# High_Side_FETs_Parallel.net
KiCad netlist of a schematic drawn in Altium Designer
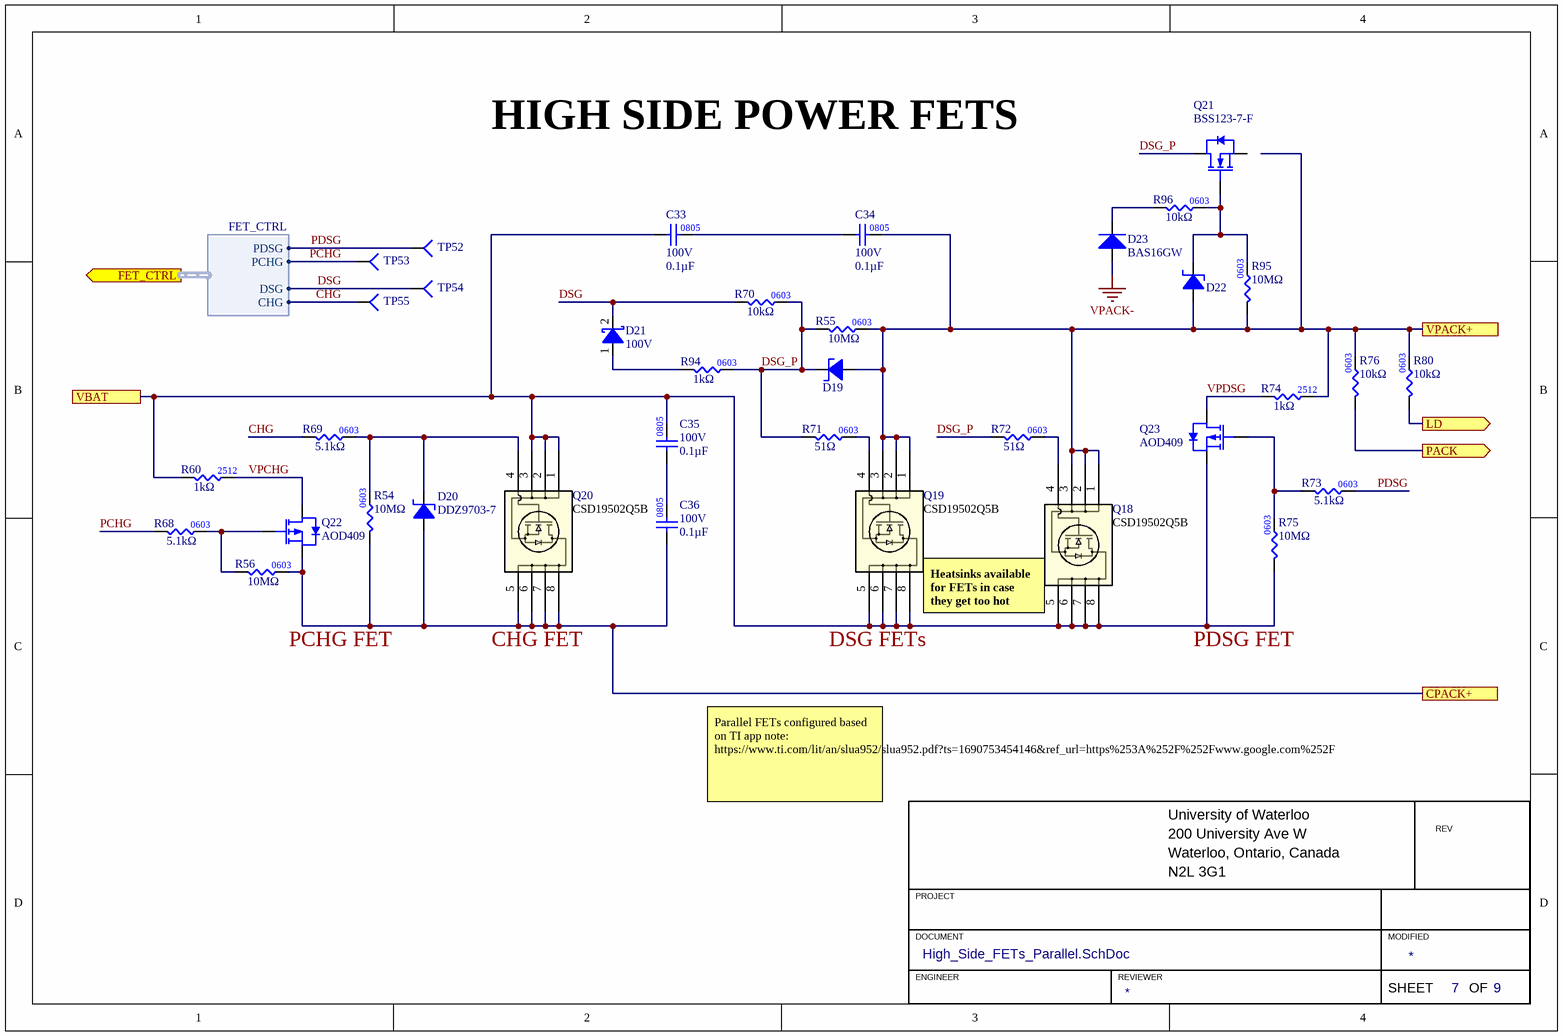
[diagram p0: High_Side_FETs_Parallel.SchDoc]

(export (version "E")
  (design (tool "Eeschema 10.0.6"))
  (components
    (comp (ref "C33")
      (value "0.1µF")
      (footprint "CAP0805")
      (description "CAP CER 0.1UF 100V X7R 0805")
      (fields (field (name "VOLTAGE RATING") "100V") (field (name "Comment") "CAP_0.1uF_100V_0805"))
      (libsource (lib "Personal_Schematic_Library_2022") (part "CAP_0.1uF_100V_0805"))
    )
    (comp (ref "C34")
      (value "0.1µF")
      (footprint "CAP0805")
      (description "CAP CER 0.1UF 100V X7R 0805")
      (fields (field (name "VOLTAGE RATING") "100V") (field (name "Comment") "CAP_0.1uF_100V_0805"))
      (libsource (lib "Personal_Schematic_Library_2022") (part "CAP_0.1uF_100V_0805"))
    )
    (comp (ref "C35")
      (value "0.1µF")
      (footprint "CAP0805")
      (description "CAP CER 0.1UF 100V X7R 0805")
      (fields (field (name "VOLTAGE RATING") "100V") (field (name "Comment") "CAP_0.1uF_100V_0805"))
      (libsource (lib "Personal_Schematic_Library_2022") (part "CAP_0.1uF_100V_0805"))
    )
    (comp (ref "C36")
      (value "0.1µF")
      (footprint "CAP0805")
      (description "CAP CER 0.1UF 100V X7R 0805")
      (fields (field (name "VOLTAGE RATING") "100V") (field (name "Comment") "CAP_0.1uF_100V_0805"))
      (libsource (lib "Personal_Schematic_Library_2022") (part "CAP_0.1uF_100V_0805"))
    )
    (comp (ref "D19")
      (value "DIO_ZENER_16V")
      (footprint "SOD-123_FLAT")
      (description "DIODE ZENER 16V 500MW SOD123")
      (libsource (lib "Personal_Schematic_Library_2022") (part "DIO_ZENER_16V"))
    )
    (comp (ref "D20")
      (value "DIO_ZENER_16V")
      (footprint "SOD-123_FLAT")
      (description "DIODE ZENER 16V 500MW SOD123")
      (fields (field (name "MANUFACTURER PART NUMBER 1") "DDZ9703-7"))
      (libsource (lib "Personal_Schematic_Library_2022") (part "DIO_ZENER_16V"))
    )
    (comp (ref "D21")
      (value "DIO_SCHOTTKY_100V_1A")
      (footprint "SOD-123_FLAT")
      (description "DIODE SCHOTTKY 100V 1A SOD-123F")
      (fields (field (name "VR (MAX)") "100V"))
      (libsource (lib "Personal_Schematic_Library_2022") (part "DIO_SCHOTTKY_100V_1A"))
    )
    (comp (ref "D22")
      (value "DIO_ZENER_16V")
      (footprint "SOD-123_FLAT")
      (description "DIODE ZENER 16V 500MW SOD123")
      (libsource (lib "Personal_Schematic_Library_2022") (part "DIO_ZENER_16V"))
    )
    (comp (ref "D23")
      (value "DIO_100V_215mA")
      (footprint "DIODSOD-123")
      (description "DIODE GEN PURP 100V 215MA SOD123")
      (fields (field (name "MANUFACTURER PART NUMBER 1") "BAS16GW"))
      (libsource (lib "Personal_Schematic_Library_2022") (part "DIO_100V_215mA"))
    )
    (comp (ref "Q18")
      (value "CSD19502Q5B")
      (footprint "DFN5060")
      (description "MOSFET N-CH 80V 100A 8VSON")
      (fields (field (name "MANUFACTURER PART NUMBER 1") "CSD19502Q5B"))
      (libsource (lib "Personal_Schematic_Library_2022") (part "NMOS_CSD19502Q5B_80V_100A"))
    )
    (comp (ref "Q19")
      (value "CSD19502Q5B")
      (footprint "DFN5060")
      (description "MOSFET N-CH 80V 100A 8VSON")
      (fields (field (name "MANUFACTURER PART NUMBER 1") "CSD19502Q5B"))
      (libsource (lib "Personal_Schematic_Library_2022") (part "NMOS_CSD19502Q5B_80V_100A"))
    )
    (comp (ref "Q20")
      (value "CSD19502Q5B")
      (footprint "DFN5060")
      (description "MOSFET N-CH 80V 100A 8VSON")
      (fields (field (name "MANUFACTURER PART NUMBER 1") "CSD19502Q5B"))
      (libsource (lib "Personal_Schematic_Library_2022") (part "NMOS_CSD19502Q5B_80V_100A"))
    )
    (comp (ref "Q21")
      (value "NMOS_100V_170mA")
      (footprint "SOT23-3")
      (description "MOSFET N-CH 100V 170MA SOT23-3")
      (fields (field (name "MANUFACTURER PART NUMBER 1") "BSS123-7-F"))
      (libsource (lib "Personal_Schematic_Library_2022") (part "NMOS_100V_170mA"))
    )
    (comp (ref "Q22")
      (value "PMOS_60V_26A")
      (footprint "TO-252 AOSMD")
      (description "MOSFET P-CH 60V 26A TO252")
      (fields (field (name "MANUFACTURER PART NUMBER 1") "AOD409"))
      (libsource (lib "Personal_Schematic_Library_2022") (part "PMOS_60V_26A"))
    )
    (comp (ref "Q23")
      (value "PMOS_60V_26A")
      (footprint "TO-252 AOSMD")
      (description "MOSFET P-CH 60V 26A TO252")
      (fields (field (name "MANUFACTURER PART NUMBER 1") "AOD409"))
      (libsource (lib "Personal_Schematic_Library_2022") (part "PMOS_60V_26A"))
    )
    (comp (ref "R54")
      (value "10MΩ")
      (footprint "RES0603")
      (description "RES 10M OHM 1% 1/10W 0603")
      (fields (field (name "Comment") "RES_10MΩ_0603_1%"))
      (libsource (lib "Personal_Schematic_Library_2022") (part "RES_10MΩ_0603_1%"))
    )
    (comp (ref "R55")
      (value "10MΩ")
      (footprint "RES0603")
      (description "RES 10M OHM 1% 1/10W 0603")
      (fields (field (name "Comment") "RES_10MΩ_0603_1%"))
      (libsource (lib "Personal_Schematic_Library_2022") (part "RES_10MΩ_0603_1%"))
    )
    (comp (ref "R56")
      (value "10MΩ")
      (footprint "RES0603")
      (description "RES 10M OHM 1% 1/10W 0603")
      (fields (field (name "Comment") "RES_10MΩ_0603_1%"))
      (libsource (lib "Personal_Schematic_Library_2022") (part "RES_10MΩ_0603_1%"))
    )
    (comp (ref "R60")
      (value "1kΩ")
      (footprint "RES2512")
      (description "RES SMD 1K OHM 1% 3W 2512")
      (fields (field (name "Comment") "RES_1kΩ_2512_1%"))
      (libsource (lib "Personal_Schematic_Library_2022") (part "RES_1kΩ_2512_1%"))
    )
    (comp (ref "R68")
      (value "5.1kΩ")
      (footprint "RES0603")
      (description "RES 5.1K OHM 1% 1/10W 0603")
      (fields (field (name "Comment") "RES_5.1kΩ_0603_1%"))
      (libsource (lib "Personal_Schematic_Library_2022") (part "RES_5.1kΩ_0603_1%"))
    )
    (comp (ref "R69")
      (value "5.1kΩ")
      (footprint "RES0603")
      (description "RES 5.1K OHM 1% 1/10W 0603")
      (fields (field (name "Comment") "RES_5.1kΩ_0603_1%"))
      (libsource (lib "Personal_Schematic_Library_2022") (part "RES_5.1kΩ_0603_1%"))
    )
    (comp (ref "R70")
      (value "10kΩ")
      (footprint "RES0603")
      (description "RES 10K OHM 1% 1/8W 0603")
      (fields (field (name "Comment") "RES_10kΩ_0603_1%"))
      (libsource (lib "Personal_Schematic_Library_2022") (part "RES_10kΩ_0603_1%"))
    )
    (comp (ref "R71")
      (value "51Ω")
      (footprint "RES0603")
      (description "RES 51 OHM 1% 1/10W 0603")
      (fields (field (name "Comment") "RES_51Ω_0603_1%"))
      (libsource (lib "Personal_Schematic_Library_2022") (part "RES_51Ω_0603_1%"))
    )
    (comp (ref "R72")
      (value "51Ω")
      (footprint "RES0603")
      (description "RES 51 OHM 1% 1/10W 0603")
      (fields (field (name "Comment") "RES_51Ω_0603_1%"))
      (libsource (lib "Personal_Schematic_Library_2022") (part "RES_51Ω_0603_1%"))
    )
    (comp (ref "R73")
      (value "5.1kΩ")
      (footprint "RES0603")
      (description "RES 5.1K OHM 1% 1/10W 0603")
      (fields (field (name "Comment") "RES_5.1kΩ_0603_1%"))
      (libsource (lib "Personal_Schematic_Library_2022") (part "RES_5.1kΩ_0603_1%"))
    )
    (comp (ref "R74")
      (value "1kΩ")
      (footprint "RES2512")
      (description "RES SMD 1K OHM 1% 3W 2512")
      (fields (field (name "Comment") "RES_1kΩ_2512_1%"))
      (libsource (lib "Personal_Schematic_Library_2022") (part "RES_1kΩ_2512_1%"))
    )
    (comp (ref "R75")
      (value "10MΩ")
      (footprint "RES0603")
      (description "RES 10M OHM 1% 1/10W 0603")
      (fields (field (name "Comment") "RES_10MΩ_0603_1%"))
      (libsource (lib "Personal_Schematic_Library_2022") (part "RES_10MΩ_0603_1%"))
    )
    (comp (ref "R76")
      (value "10kΩ")
      (footprint "RES0603")
      (description "RES 10K OHM 1% 1/8W 0603")
      (fields (field (name "Comment") "RES_10kΩ_0603_1%"))
      (libsource (lib "Personal_Schematic_Library_2022") (part "RES_10kΩ_0603_1%"))
    )
    (comp (ref "R80")
      (value "10kΩ")
      (footprint "RES0603")
      (description "RES 10K OHM 1% 1/8W 0603")
      (fields (field (name "Comment") "RES_10kΩ_0603_1%"))
      (libsource (lib "Personal_Schematic_Library_2022") (part "RES_10kΩ_0603_1%"))
    )
    (comp (ref "R94")
      (value "1kΩ")
      (footprint "RES0603")
      (description "RES 1K OHM 1% 1/8W 0603")
      (fields (field (name "Comment") "RES_1kΩ_0603_1%"))
      (libsource (lib "Personal_Schematic_Library_2022") (part "RES_1kΩ_0603_1%"))
    )
    (comp (ref "R95")
      (value "10MΩ")
      (footprint "RES0603")
      (description "RES 10M OHM 1% 1/10W 0603")
      (fields (field (name "Comment") "RES_10MΩ_0603_1%"))
      (libsource (lib "Personal_Schematic_Library_2022") (part "RES_10MΩ_0603_1%"))
    )
    (comp (ref "R96")
      (value "10kΩ")
      (footprint "RES0603")
      (description "RES 10K OHM 1% 1/8W 0603")
      (fields (field (name "Comment") "RES_10kΩ_0603_1%"))
      (libsource (lib "Personal_Schematic_Library_2022") (part "RES_10kΩ_0603_1%"))
    )
    (comp (ref "TP52")
      (value "TESTPOINT_1MM_CIRCLE")
      (footprint "TESTPOINT_CIRCLE_1MM")
      (description "TESTPOINT 1MM CIRCLE")
      (libsource (lib "Personal_Schematic_Library_2022") (part "TESTPOINT_1MM_CIRCLE"))
    )
    (comp (ref "TP53")
      (value "TESTPOINT_1MM_CIRCLE")
      (footprint "TESTPOINT_CIRCLE_1MM")
      (description "TESTPOINT 1MM CIRCLE")
      (libsource (lib "Personal_Schematic_Library_2022") (part "TESTPOINT_1MM_CIRCLE"))
    )
    (comp (ref "TP54")
      (value "TESTPOINT_1MM_CIRCLE")
      (footprint "TESTPOINT_CIRCLE_1MM")
      (description "TESTPOINT 1MM CIRCLE")
      (libsource (lib "Personal_Schematic_Library_2022") (part "TESTPOINT_1MM_CIRCLE"))
    )
    (comp (ref "TP55")
      (value "TESTPOINT_1MM_CIRCLE")
      (footprint "TESTPOINT_CIRCLE_1MM")
      (description "TESTPOINT 1MM CIRCLE")
      (libsource (lib "Personal_Schematic_Library_2022") (part "TESTPOINT_1MM_CIRCLE"))
    )
  )
  (nets
    (net (code "2") (name "/CHG") (class "Default")
      (node (ref "R69") (pin "1") (pinfunction "1_1") (pintype "passive"))
      (node (ref "TP55") (pin "1") (pinfunction "=value_1") (pintype "passive"))
    )
    (net (code "3") (name "/CPACK+") (class "Default")
      (node (ref "C36") (pin "1") (pinfunction "1_1") (pintype "passive"))
      (node (ref "D20") (pin "1") (pinfunction "Anode_1") (pintype "passive"))
      (node (ref "Q20") (pin "5") (pinfunction "D_5") (pintype "passive"))
      (node (ref "Q20") (pin "6") (pinfunction "D_6") (pintype "passive"))
      (node (ref "Q20") (pin "7") (pinfunction "D_7") (pintype "passive"))
      (node (ref "Q20") (pin "8") (pinfunction "D_8") (pintype "passive"))
      (node (ref "Q22") (pin "3") (pinfunction "Source_3") (pintype "passive"))
      (node (ref "R54") (pin "1") (pinfunction "1_1") (pintype "passive"))
      (node (ref "R56") (pin "2") (pinfunction "2_2") (pintype "passive"))
    )
    (net (code "4") (name "/DSG") (class "Default")
      (node (ref "D21") (pin "2") (pinfunction "Cathode_2") (pintype "passive"))
      (node (ref "R70") (pin "1") (pinfunction "1_1") (pintype "passive"))
      (node (ref "TP54") (pin "1") (pinfunction "=value_1") (pintype "passive"))
    )
    (net (code "5") (name "/DSG_P") (class "Default")
      (node (ref "D19") (pin "2") (pinfunction "Cathode_2") (pintype "passive"))
      (node (ref "Q21") (pin "3") (pinfunction "DRAIN_3") (pintype "passive"))
      (node (ref "R55") (pin "1") (pinfunction "1_1") (pintype "passive"))
      (node (ref "R70") (pin "2") (pinfunction "2_2") (pintype "passive"))
      (node (ref "R71") (pin "1") (pinfunction "1_1") (pintype "passive"))
      (node (ref "R72") (pin "1") (pinfunction "1_1") (pintype "passive"))
      (node (ref "R94") (pin "2") (pinfunction "2_2") (pintype "passive"))
    )
    (net (code "6") (name "/LD") (class "Default")
      (node (ref "R80") (pin "1") (pinfunction "1_1") (pintype "passive"))
    )
    (net (code "7") (name "/PACK") (class "Default")
      (node (ref "R76") (pin "1") (pinfunction "1_1") (pintype "passive"))
    )
    (net (code "8") (name "/PCHG") (class "Default")
      (node (ref "R68") (pin "1") (pinfunction "1_1") (pintype "passive"))
      (node (ref "TP53") (pin "1") (pinfunction "=value_1") (pintype "passive"))
    )
    (net (code "9") (name "/PDSG") (class "Default")
      (node (ref "R73") (pin "2") (pinfunction "2_2") (pintype "passive"))
      (node (ref "TP52") (pin "1") (pinfunction "=value_1") (pintype "passive"))
    )
    (net (code "10") (name "/VBAT") (class "Default")
      (node (ref "C33") (pin "1") (pinfunction "1_1") (pintype "passive"))
      (node (ref "C35") (pin "2") (pinfunction "2_2") (pintype "passive"))
      (node (ref "Q18") (pin "5") (pinfunction "D_5") (pintype "passive"))
      (node (ref "Q18") (pin "6") (pinfunction "D_6") (pintype "passive"))
      (node (ref "Q18") (pin "7") (pinfunction "D_7") (pintype "passive"))
      (node (ref "Q18") (pin "8") (pinfunction "D_8") (pintype "passive"))
      (node (ref "Q19") (pin "5") (pinfunction "D_5") (pintype "passive"))
      (node (ref "Q19") (pin "6") (pinfunction "D_6") (pintype "passive"))
      (node (ref "Q19") (pin "7") (pinfunction "D_7") (pintype "passive"))
      (node (ref "Q19") (pin "8") (pinfunction "D_8") (pintype "passive"))
      (node (ref "Q20") (pin "1") (pinfunction "S_1") (pintype "passive"))
      (node (ref "Q20") (pin "2") (pinfunction "S_2") (pintype "passive"))
      (node (ref "Q20") (pin "3") (pinfunction "S_3") (pintype "passive"))
      (node (ref "Q23") (pin "3") (pinfunction "Source_3") (pintype "passive"))
      (node (ref "R60") (pin "1") (pinfunction "1_1") (pintype "passive"))
      (node (ref "R75") (pin "1") (pinfunction "1_1") (pintype "passive"))
    )
    (net (code "11") (name "/VPACK+") (class "Default")
      (node (ref "C34") (pin "2") (pinfunction "2_2") (pintype "passive"))
      (node (ref "D19") (pin "1") (pinfunction "Anode_1") (pintype "passive"))
      (node (ref "D22") (pin "1") (pinfunction "Anode_1") (pintype "passive"))
      (node (ref "Q18") (pin "1") (pinfunction "S_1") (pintype "passive"))
      (node (ref "Q18") (pin "2") (pinfunction "S_2") (pintype "passive"))
      (node (ref "Q18") (pin "3") (pinfunction "S_3") (pintype "passive"))
      (node (ref "Q19") (pin "1") (pinfunction "S_1") (pintype "passive"))
      (node (ref "Q19") (pin "2") (pinfunction "S_2") (pintype "passive"))
      (node (ref "Q19") (pin "3") (pinfunction "S_3") (pintype "passive"))
      (node (ref "R55") (pin "2") (pinfunction "2_2") (pintype "passive"))
      (node (ref "R74") (pin "2") (pinfunction "2_2") (pintype "passive"))
      (node (ref "R76") (pin "2") (pinfunction "2_2") (pintype "passive"))
      (node (ref "R80") (pin "2") (pinfunction "2_2") (pintype "passive"))
      (node (ref "R95") (pin "1") (pinfunction "1_1") (pintype "passive"))
    )
    (net (code "12") (name "/VPCHG") (class "Default")
      (node (ref "Q22") (pin "2") (pinfunction "Drain_2") (pintype "passive"))
      (node (ref "R60") (pin "2") (pinfunction "2_2") (pintype "passive"))
    )
    (net (code "13") (name "/VPDSG") (class "Default")
      (node (ref "Q23") (pin "2") (pinfunction "Drain_2") (pintype "passive"))
      (node (ref "R74") (pin "1") (pinfunction "1_1") (pintype "passive"))
    )
    (net (code "15") (name "Net-(C33-Pad2)") (class "Default")
      (node (ref "C33") (pin "2") (pinfunction "2_2") (pintype "passive"))
      (node (ref "C34") (pin "1") (pinfunction "1_1") (pintype "passive"))
    )
    (net (code "16") (name "Net-(C35-Pad1)") (class "Default")
      (node (ref "C35") (pin "1") (pinfunction "1_1") (pintype "passive"))
      (node (ref "C36") (pin "2") (pinfunction "2_2") (pintype "passive"))
    )
    (net (code "17") (name "Net-(D20-Cathode)") (class "Default")
      (node (ref "D20") (pin "2") (pinfunction "Cathode_2") (pintype "passive"))
      (node (ref "Q20") (pin "4") (pinfunction "G_4") (pintype "passive"))
      (node (ref "R54") (pin "2") (pinfunction "2_2") (pintype "passive"))
      (node (ref "R69") (pin "2") (pinfunction "2_2") (pintype "passive"))
    )
    (net (code "18") (name "Net-(D21-Anode)") (class "Default")
      (node (ref "D21") (pin "1") (pinfunction "Anode_1") (pintype "passive"))
      (node (ref "R94") (pin "1") (pinfunction "1_1") (pintype "passive"))
    )
    (net (code "19") (name "Net-(D22-Cathode)") (class "Default")
      (node (ref "D22") (pin "2") (pinfunction "Cathode_2") (pintype "passive"))
      (node (ref "Q21") (pin "1") (pinfunction "GATE_1") (pintype "passive"))
      (node (ref "R95") (pin "2") (pinfunction "2_2") (pintype "passive"))
      (node (ref "R96") (pin "2") (pinfunction "2_2") (pintype "passive"))
    )
    (net (code "20") (name "Net-(D23-K)") (class "Default")
      (node (ref "D23") (pin "2") (pinfunction "K_2") (pintype "passive"))
      (node (ref "R96") (pin "1") (pinfunction "1_1") (pintype "passive"))
    )
    (net (code "21") (name "Net-(Q18-G)") (class "Default")
      (node (ref "Q18") (pin "4") (pinfunction "G_4") (pintype "passive"))
      (node (ref "R72") (pin "2") (pinfunction "2_2") (pintype "passive"))
    )
    (net (code "22") (name "Net-(Q19-G)") (class "Default")
      (node (ref "Q19") (pin "4") (pinfunction "G_4") (pintype "passive"))
      (node (ref "R71") (pin "2") (pinfunction "2_2") (pintype "passive"))
    )
    (net (code "23") (name "Net-(Q22-Gate)") (class "Default")
      (node (ref "Q22") (pin "1") (pinfunction "Gate_1") (pintype "passive"))
      (node (ref "R56") (pin "1") (pinfunction "1_1") (pintype "passive"))
      (node (ref "R68") (pin "2") (pinfunction "2_2") (pintype "passive"))
    )
    (net (code "24") (name "Net-(Q23-Gate)") (class "Default")
      (node (ref "Q23") (pin "1") (pinfunction "Gate_1") (pintype "passive"))
      (node (ref "R73") (pin "1") (pinfunction "1_1") (pintype "passive"))
      (node (ref "R75") (pin "2") (pinfunction "2_2") (pintype "passive"))
    )
    (net (code "25") (name "VPACK-") (class "Default")
      (node (ref "D23") (pin "1") (pinfunction "A_1") (pintype "passive"))
    )
    (net (code "26") (name "unconnected-(Q21-SOURCE-Pad2)") (class "Default")
      (node (ref "Q21") (pin "2") (pinfunction "SOURCE_2") (pintype "passive"))
    )
  )
)
